# Schematic.net
KiCad netlist of a schematic drawn in EAGLE
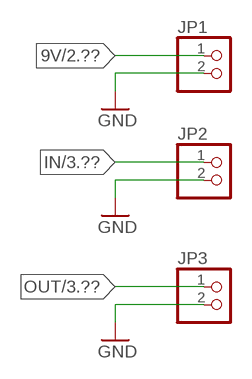
[diagram p0: schematic, sheet 1]
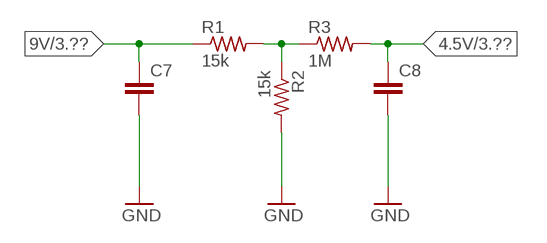
[diagram p1: schematic, sheet 2]
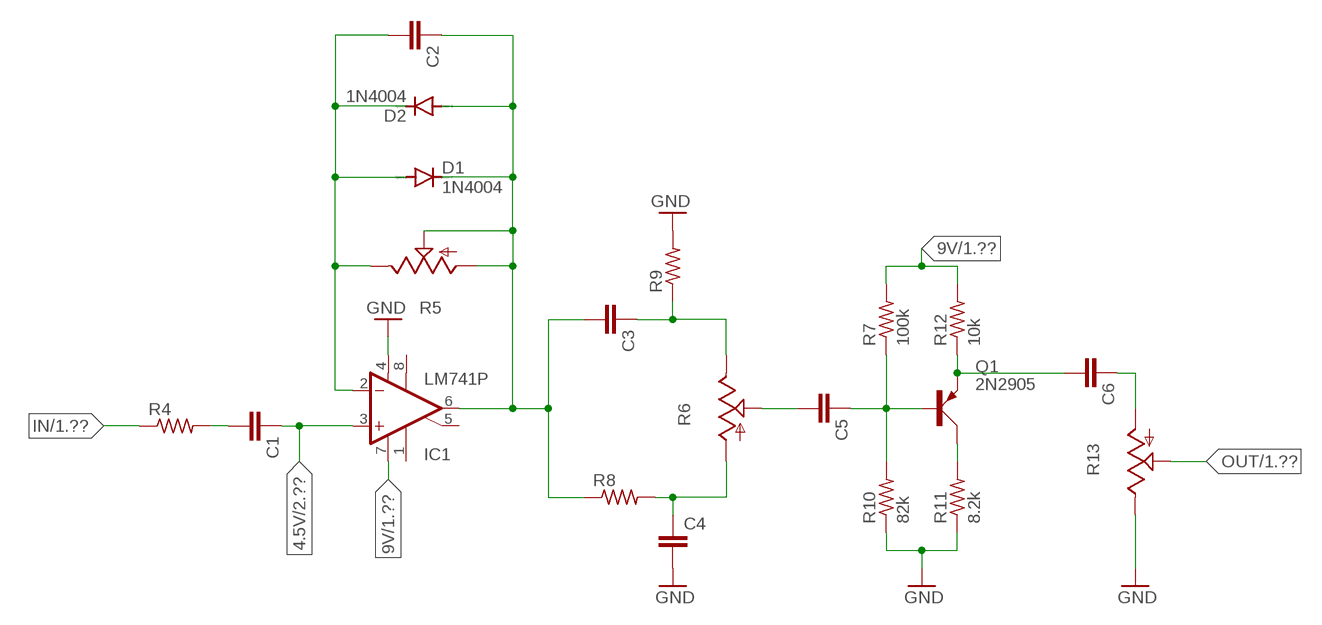
[diagram p2: schematic, sheet 3]

(export (version "E")
  (design (tool "Eeschema 10.0.6"))
  (components
    (comp (ref "JP1")
      (value "PINHD-1X2")
      (footprint "eagle-import:1X02")
      (libsource (lib "eagle-import") (part "PINHD-1X2"))
    )
    (comp (ref "JP2")
      (value "PINHD-1X2")
      (footprint "eagle-import:1X02")
      (libsource (lib "eagle-import") (part "PINHD-1X2"))
    )
    (comp (ref "JP3")
      (value "PINHD-1X2")
      (footprint "eagle-import:1X02")
      (libsource (lib "eagle-import") (part "PINHD-1X2"))
    )
    (comp (ref "C1")
      (value "C-EU025-025X050")
      (footprint "eagle-import:C025-025X050")
      (libsource (lib "eagle-import") (part "C-EU025-025X050"))
    )
    (comp (ref "C2")
      (value "C-EU025-025X050")
      (footprint "eagle-import:C025-025X050")
      (libsource (lib "eagle-import") (part "C-EU025-025X050"))
    )
    (comp (ref "C3")
      (value "C-EU025-025X050")
      (footprint "eagle-import:C025-025X050")
      (libsource (lib "eagle-import") (part "C-EU025-025X050"))
    )
    (comp (ref "C4")
      (value "C-EU025-025X050")
      (footprint "eagle-import:C025-025X050")
      (libsource (lib "eagle-import") (part "C-EU025-025X050"))
    )
    (comp (ref "C5")
      (value "C-EU025-025X050")
      (footprint "eagle-import:C025-025X050")
      (libsource (lib "eagle-import") (part "C-EU025-025X050"))
    )
    (comp (ref "C6")
      (value "C-EU025-025X050")
      (footprint "eagle-import:C025-025X050")
      (libsource (lib "eagle-import") (part "C-EU025-025X050"))
    )
    (comp (ref "D1")
      (value "1N4004")
      (footprint "eagle-import:DO41-10")
      (libsource (lib "eagle-import") (part "1N4004"))
    )
    (comp (ref "D2")
      (value "1N4004")
      (footprint "eagle-import:DO41-10")
      (libsource (lib "eagle-import") (part "1N4004"))
    )
    (comp (ref "IC1")
      (value "LM741P")
      (footprint "eagle-import:DIL08")
      (libsource (lib "eagle-import") (part "741PLM"))
    )
    (comp (ref "Q1")
      (value "2N2905")
      (footprint "eagle-import:TO39")
      (libsource (lib "eagle-import") (part "2N2905"))
    )
    (comp (ref "R4")
      (value "R-US_0204/7")
      (footprint "eagle-import:0204_7")
      (libsource (lib "eagle-import") (part "R-US_0204/7"))
    )
    (comp (ref "R5")
      (value "TRIM_US-B64Y")
      (footprint "eagle-import:B64Y")
      (libsource (lib "eagle-import") (part "TRIM_US-B64Y"))
    )
    (comp (ref "R6")
      (value "TRIM_US-B64Y")
      (footprint "eagle-import:B64Y")
      (libsource (lib "eagle-import") (part "TRIM_US-B64Y"))
    )
    (comp (ref "R7")
      (value "100k")
      (footprint "eagle-import:0204_7")
      (libsource (lib "eagle-import") (part "R-US_0204/7"))
    )
    (comp (ref "R8")
      (value "R-US_0204/7")
      (footprint "eagle-import:0204_7")
      (libsource (lib "eagle-import") (part "R-US_0204/7"))
    )
    (comp (ref "R9")
      (value "R-US_0204/7")
      (footprint "eagle-import:0204_7")
      (libsource (lib "eagle-import") (part "R-US_0204/7"))
    )
    (comp (ref "R10")
      (value "82k")
      (footprint "eagle-import:0204_7")
      (libsource (lib "eagle-import") (part "R-US_0204/7"))
    )
    (comp (ref "R11")
      (value "8.2k")
      (footprint "eagle-import:0204_7")
      (libsource (lib "eagle-import") (part "R-US_0204/7"))
    )
    (comp (ref "R12")
      (value "10k")
      (footprint "eagle-import:0204_7")
      (libsource (lib "eagle-import") (part "R-US_0204/7"))
    )
    (comp (ref "R13")
      (value "TRIM_US-B64Y")
      (footprint "eagle-import:B64Y")
      (libsource (lib "eagle-import") (part "TRIM_US-B64Y"))
    )
    (comp (ref "C7")
      (value "C-EU025-025X050")
      (footprint "eagle-import:C025-025X050")
      (libsource (lib "eagle-import") (part "C-EU025-025X050"))
    )
    (comp (ref "C8")
      (value "C-EU025-025X050")
      (footprint "eagle-import:C025-025X050")
      (libsource (lib "eagle-import") (part "C-EU025-025X050"))
    )
    (comp (ref "R1")
      (value "15k")
      (footprint "eagle-import:0204_7")
      (libsource (lib "eagle-import") (part "R-US_0204/7"))
    )
    (comp (ref "R2")
      (value "15k")
      (footprint "eagle-import:0204_7")
      (libsource (lib "eagle-import") (part "R-US_0204/7"))
    )
    (comp (ref "R3")
      (value "1M")
      (footprint "eagle-import:0204_7")
      (libsource (lib "eagle-import") (part "R-US_0204/7"))
    )
  )
  (nets
    (net (code "1") (name "4.5V") (class "Default")
      (node (ref "C1") (pin "1") (pinfunction "1_1") (pintype "passive"))
      (node (ref "C8") (pin "1") (pinfunction "1_1") (pintype "passive"))
      (node (ref "IC1") (pin "3") (pinfunction "+IN_3") (pintype "input"))
      (node (ref "R3") (pin "2") (pinfunction "2_2") (pintype "passive"))
    )
    (net (code "2") (name "9V") (class "Default")
      (node (ref "C7") (pin "1") (pinfunction "1_1") (pintype "passive"))
      (node (ref "IC1") (pin "7") (pinfunction "V+_7") (pintype "power_in"))
      (node (ref "JP1") (pin "1") (pinfunction "1_1") (pintype "passive"))
      (node (ref "R1") (pin "1") (pinfunction "1_1") (pintype "passive"))
      (node (ref "R12") (pin "2") (pinfunction "2_2") (pintype "passive"))
      (node (ref "R7") (pin "2") (pinfunction "2_2") (pintype "passive"))
    )
    (net (code "3") (name "GND") (class "Default")
      (node (ref "C4") (pin "2") (pinfunction "2_2") (pintype "passive"))
      (node (ref "C7") (pin "2") (pinfunction "2_2") (pintype "passive"))
      (node (ref "C8") (pin "2") (pinfunction "2_2") (pintype "passive"))
      (node (ref "IC1") (pin "4") (pinfunction "V-_4") (pintype "power_in"))
      (node (ref "JP1") (pin "2") (pinfunction "2_2") (pintype "passive"))
      (node (ref "JP2") (pin "2") (pinfunction "2_2") (pintype "passive"))
      (node (ref "JP3") (pin "2") (pinfunction "2_2") (pintype "passive"))
      (node (ref "R10") (pin "1") (pinfunction "1_1") (pintype "passive"))
      (node (ref "R11") (pin "1") (pinfunction "1_1") (pintype "passive"))
      (node (ref "R13") (pin "E") (pinfunction "E_E") (pintype "passive"))
      (node (ref "R2") (pin "2") (pinfunction "2_2") (pintype "passive"))
      (node (ref "R9") (pin "2") (pinfunction "2_2") (pintype "passive"))
    )
    (net (code "4") (name "IN") (class "Default")
      (node (ref "JP2") (pin "1") (pinfunction "1_1") (pintype "passive"))
      (node (ref "R4") (pin "1") (pinfunction "1_1") (pintype "passive"))
    )
    (net (code "5") (name "Net-(C1-Pad2)") (class "Default")
      (node (ref "C1") (pin "2") (pinfunction "2_2") (pintype "passive"))
      (node (ref "R4") (pin "2") (pinfunction "2_2") (pintype "passive"))
    )
    (net (code "6") (name "Net-(C3-Pad1)") (class "Default")
      (node (ref "C3") (pin "1") (pinfunction "1_1") (pintype "passive"))
      (node (ref "R6") (pin "E") (pinfunction "E_E") (pintype "passive"))
      (node (ref "R9") (pin "1") (pinfunction "1_1") (pintype "passive"))
    )
    (net (code "7") (name "Net-(C4-Pad1)") (class "Default")
      (node (ref "C4") (pin "1") (pinfunction "1_1") (pintype "passive"))
      (node (ref "R6") (pin "A") (pinfunction "A_A") (pintype "passive"))
      (node (ref "R8") (pin "2") (pinfunction "2_2") (pintype "passive"))
    )
    (net (code "8") (name "Net-(C5-Pad2)") (class "Default")
      (node (ref "C5") (pin "2") (pinfunction "2_2") (pintype "passive"))
      (node (ref "R6") (pin "S") (pinfunction "S_S") (pintype "passive"))
    )
    (net (code "9") (name "Net-(C6-Pad1)") (class "Default")
      (node (ref "C6") (pin "1") (pinfunction "1_1") (pintype "passive"))
      (node (ref "R13") (pin "A") (pinfunction "A_A") (pintype "passive"))
    )
    (net (code "10") (name "Net-(IC1--IN)") (class "Default")
      (node (ref "C2") (pin "2") (pinfunction "2_2") (pintype "passive"))
      (node (ref "D1") (pin "A") (pinfunction "A_A") (pintype "passive"))
      (node (ref "D2") (pin "C") (pinfunction "C_C") (pintype "passive"))
      (node (ref "IC1") (pin "2") (pinfunction "-IN_2") (pintype "input"))
      (node (ref "R5") (pin "E") (pinfunction "E_E") (pintype "passive"))
    )
    (net (code "11") (name "Net-(IC1-OUT)") (class "Default")
      (node (ref "C2") (pin "1") (pinfunction "1_1") (pintype "passive"))
      (node (ref "C3") (pin "2") (pinfunction "2_2") (pintype "passive"))
      (node (ref "D1") (pin "C") (pinfunction "C_C") (pintype "passive"))
      (node (ref "D2") (pin "A") (pinfunction "A_A") (pintype "passive"))
      (node (ref "IC1") (pin "6") (pinfunction "OUT_6") (pintype "output"))
      (node (ref "R5") (pin "A") (pinfunction "A_A") (pintype "passive"))
      (node (ref "R5") (pin "S") (pinfunction "S_S") (pintype "passive"))
      (node (ref "R8") (pin "1") (pinfunction "1_1") (pintype "passive"))
    )
    (net (code "12") (name "Net-(Q1-B)") (class "Default")
      (node (ref "C5") (pin "1") (pinfunction "1_1") (pintype "passive"))
      (node (ref "Q1") (pin "2") (pinfunction "B_2") (pintype "passive"))
      (node (ref "R10") (pin "2") (pinfunction "2_2") (pintype "passive"))
      (node (ref "R7") (pin "1") (pinfunction "1_1") (pintype "passive"))
    )
    (net (code "13") (name "Net-(Q1-C)") (class "Default")
      (node (ref "Q1") (pin "3") (pinfunction "C_3") (pintype "passive"))
      (node (ref "R11") (pin "2") (pinfunction "2_2") (pintype "passive"))
    )
    (net (code "14") (name "Net-(Q1-E)") (class "Default")
      (node (ref "C6") (pin "2") (pinfunction "2_2") (pintype "passive"))
      (node (ref "Q1") (pin "1") (pinfunction "E_1") (pintype "passive"))
      (node (ref "R12") (pin "1") (pinfunction "1_1") (pintype "passive"))
    )
    (net (code "15") (name "Net-(R1-Pad2)") (class "Default")
      (node (ref "R1") (pin "2") (pinfunction "2_2") (pintype "passive"))
      (node (ref "R2") (pin "1") (pinfunction "1_1") (pintype "passive"))
      (node (ref "R3") (pin "1") (pinfunction "1_1") (pintype "passive"))
    )
    (net (code "16") (name "OUT") (class "Default")
      (node (ref "JP3") (pin "1") (pinfunction "1_1") (pintype "passive"))
      (node (ref "R13") (pin "S") (pinfunction "S_S") (pintype "passive"))
    )
    (net (code "17") (name "unconnected-(IC1-ON1-Pad1)") (class "Default")
      (node (ref "IC1") (pin "1") (pinfunction "ON1_1") (pintype "passive"))
    )
    (net (code "18") (name "unconnected-(IC1-ON2-Pad5)") (class "Default")
      (node (ref "IC1") (pin "5") (pinfunction "ON2_5") (pintype "passive"))
    )
    (net (code "19") (name "unconnected-(IC1-OPT-Pad8)") (class "Default")
      (node (ref "IC1") (pin "8") (pinfunction "OPT_8") (pintype "passive"))
    )
  )
)
